# DCDC_DDS.net
KiCad netlist of a schematic drawn in Altium Designer
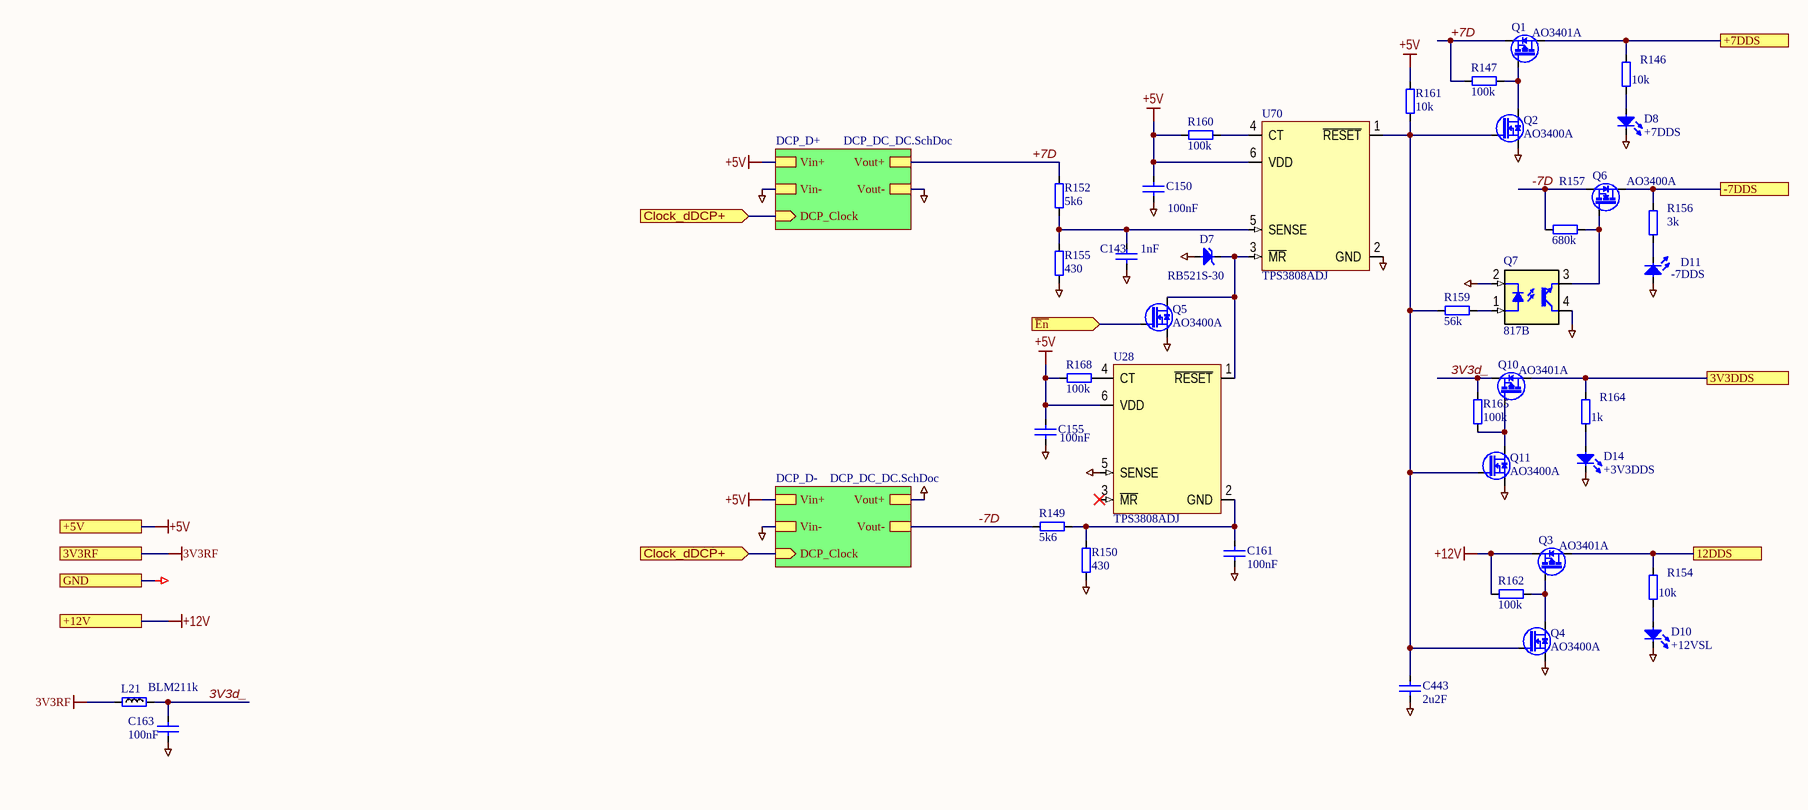
[diagram p0: DCDC_DDS.SchDoc]

(export (version "E")
  (design (tool "Eeschema 10.0.6"))
  (components
    (comp (ref "C143")
      (value "1nF")
      (footprint "SMD0805CAP")
      (description "Чип конденсатор 0805")
      (fields (field (name "VOLTAGE") "25V") (field (name "TOLERANCE") "20%"))
      (libsource (lib "DDSintLib") (part "C0805"))
    )
    (comp (ref "C150")
      (value "100nF")
      (footprint "SMD0805CAP")
      (description "Чип конденсатор 0805")
      (fields (field (name "VOLTAGE") "25V") (field (name "TOLERANCE") "20%"))
      (libsource (lib "DDSintLib") (part "C0805"))
    )
    (comp (ref "C155")
      (value "100nF")
      (footprint "SMD0805CAP")
      (description "Чип конденсатор 0805")
      (fields (field (name "VOLTAGE") "25V") (field (name "TOLERANCE") "20%"))
      (libsource (lib "DDSintLib") (part "C0805"))
    )
    (comp (ref "C161")
      (value "100nF")
      (footprint "SMD0805CAP")
      (description "Чип конденсатор 0805")
      (fields (field (name "VOLTAGE") "25V") (field (name "TOLERANCE") "20%"))
      (libsource (lib "DDSintLib") (part "C0805"))
    )
    (comp (ref "C163")
      (value "100nF")
      (footprint "SMD0805CAP")
      (description "Чип конденсатор 0805")
      (fields (field (name "VOLTAGE") "25V") (field (name "TOLERANCE") "20%"))
      (libsource (lib "DDSintLib") (part "C0805"))
    )
    (comp (ref "C443")
      (value "2u2F")
      (footprint "SMD0805CAP")
      (description "Чип конденсатор 0805")
      (fields (field (name "VOLTAGE") "25V") (field (name "TOLERANCE") "20%"))
      (libsource (lib "DDSintLib") (part "C0805"))
    )
    (comp (ref "D7")
      (value "RB521S-30")
      (footprint "SODFL1608X65N")
      (description "Чип Шоттки диод")
      (fields (field (name "VOLTAGE") "30V"))
      (libsource (lib "DDSintLib") (part "RB521S-30"))
    )
    (comp (ref "D8")
      (value "+7DDS")
      (footprint "LED0603")
      (description "Чип светодиод 0603")
      (libsource (lib "DDSintLib") (part "LED0603"))
    )
    (comp (ref "D10")
      (value "+12VSL")
      (footprint "LED0603")
      (description "Чип светодиод 0603")
      (libsource (lib "DDSintLib") (part "LED0603"))
    )
    (comp (ref "D11")
      (value "-7DDS")
      (footprint "LED0603")
      (description "Чип светодиод 0603")
      (libsource (lib "DDSintLib") (part "LED0603"))
    )
    (comp (ref "D14")
      (value "+3V3DDS")
      (footprint "LED0603")
      (description "Чип светодиод 0603")
      (libsource (lib "DDSintLib") (part "LED0603"))
    )
    (comp (ref "L21")
      (value "BLM211k")
      (footprint "RESC2012X50N")
      (description "SMD Ferrite bead 0805")
      (libsource (lib "DDSintLib") (part "BLM21"))
    )
    (comp (ref "Q1")
      (value "AO3401A")
      (footprint "SOT95P229X119-3N")
      (description "PMOS")
      (fields (field (name "VOLTAGE") "-30V"))
      (libsource (lib "DDSintLib") (part "AO3401A"))
    )
    (comp (ref "Q2")
      (value "AO3400A")
      (footprint "SOT95P229X119-3N")
      (description "NMOS")
      (fields (field (name "VOLTAGE") "30V"))
      (libsource (lib "DDSintLib") (part "AO3400A"))
    )
    (comp (ref "Q3")
      (value "AO3401A")
      (footprint "SOT95P229X119-3N")
      (description "PMOS")
      (fields (field (name "VOLTAGE") "-30V"))
      (libsource (lib "DDSintLib") (part "AO3401A"))
    )
    (comp (ref "Q4")
      (value "AO3400A")
      (footprint "SOT95P229X119-3N")
      (description "NMOS")
      (fields (field (name "VOLTAGE") "30V"))
      (libsource (lib "DDSintLib") (part "AO3400A"))
    )
    (comp (ref "Q5")
      (value "AO3400A")
      (footprint "SOT95P229X119-3N")
      (description "NMOS")
      (fields (field (name "VOLTAGE") "30V"))
      (libsource (lib "DDSintLib") (part "AO3400A"))
    )
    (comp (ref "Q6")
      (value "AO3400A")
      (footprint "SOT95P229X119-3N")
      (description "NMOS")
      (fields (field (name "VOLTAGE") "30V"))
      (libsource (lib "DDSintLib") (part "AO3400A"))
    )
    (comp (ref "Q7")
      (value "817B")
      (footprint "DIP4-300")
      (description "Optotransistor")
      (fields (field (name "VOLTAGE") "35V"))
      (libsource (lib "DDS1") (part "817B"))
    )
    (comp (ref "Q10")
      (value "AO3401A")
      (footprint "SOT95P229X119-3N")
      (description "PMOS")
      (fields (field (name "VOLTAGE") "-30V"))
      (libsource (lib "DDSintLib") (part "AO3401A"))
    )
    (comp (ref "Q11")
      (value "AO3400A")
      (footprint "SOT95P229X119-3N")
      (description "NMOS")
      (fields (field (name "VOLTAGE") "30V"))
      (libsource (lib "DDSintLib") (part "AO3400A"))
    )
    (comp (ref "R146")
      (value "10k")
      (footprint "SMD0805RES")
      (description "Чип резистор 0805")
      (fields (field (name "TOLERANCE") "1%"))
      (libsource (lib "DDSintLib") (part "R0805"))
    )
    (comp (ref "R147")
      (value "100k")
      (footprint "SMD0805RES")
      (description "Чип резистор 0805")
      (fields (field (name "TOLERANCE") "1%"))
      (libsource (lib "DDSintLib") (part "R0805"))
    )
    (comp (ref "R149")
      (value "5k6")
      (footprint "SMD0805RES")
      (description "Чип резистор 0805")
      (fields (field (name "TOLERANCE") "1%"))
      (libsource (lib "DDSintLib") (part "R0805"))
    )
    (comp (ref "R150")
      (value "430")
      (footprint "SMD0805RES")
      (description "Чип резистор 0805")
      (fields (field (name "TOLERANCE") "1%"))
      (libsource (lib "DDSintLib") (part "R0805"))
    )
    (comp (ref "R152")
      (value "5k6")
      (footprint "SMD0805RES")
      (description "Чип резистор 0805")
      (fields (field (name "TOLERANCE") "1%"))
      (libsource (lib "DDSintLib") (part "R0805"))
    )
    (comp (ref "R154")
      (value "10k")
      (footprint "SMD0805RES")
      (description "Чип резистор 0805")
      (fields (field (name "TOLERANCE") "1%"))
      (libsource (lib "DDSintLib") (part "R0805"))
    )
    (comp (ref "R155")
      (value "430")
      (footprint "SMD0805RES")
      (description "Чип резистор 0805")
      (fields (field (name "TOLERANCE") "1%"))
      (libsource (lib "DDSintLib") (part "R0805"))
    )
    (comp (ref "R156")
      (value "3k")
      (footprint "SMD0805RES")
      (description "Чип резистор 0805")
      (fields (field (name "TOLERANCE") "1%"))
      (libsource (lib "DDSintLib") (part "R0805"))
    )
    (comp (ref "R157")
      (value "680k")
      (footprint "SMD0805RES")
      (description "Чип резистор 0805")
      (fields (field (name "TOLERANCE") "1%"))
      (libsource (lib "DDSintLib") (part "R0805"))
    )
    (comp (ref "R159")
      (value "56k")
      (footprint "SMD0805RES")
      (description "Чип резистор 0805")
      (fields (field (name "TOLERANCE") "1%"))
      (libsource (lib "DDSintLib") (part "R0805"))
    )
    (comp (ref "R160")
      (value "100k")
      (footprint "SMD0805RES")
      (description "Чип резистор 0805")
      (fields (field (name "TOLERANCE") "1%"))
      (libsource (lib "DDSintLib") (part "R0805"))
    )
    (comp (ref "R161")
      (value "10k")
      (footprint "SMD0805RES")
      (description "Чип резистор 0805")
      (fields (field (name "TOLERANCE") "1%"))
      (libsource (lib "DDSintLib") (part "R0805"))
    )
    (comp (ref "R162")
      (value "100k")
      (footprint "SMD0805RES")
      (description "Чип резистор 0805")
      (fields (field (name "TOLERANCE") "1%"))
      (libsource (lib "DDSintLib") (part "R0805"))
    )
    (comp (ref "R164")
      (value "1k")
      (footprint "SMD0805RES")
      (description "Чип резистор 0805")
      (fields (field (name "TOLERANCE") "1%"))
      (libsource (lib "DDSintLib") (part "R0805"))
    )
    (comp (ref "R165")
      (value "100k")
      (footprint "SMD0805RES")
      (description "Чип резистор 0805")
      (fields (field (name "TOLERANCE") "1%"))
      (libsource (lib "DDSintLib") (part "R0805"))
    )
    (comp (ref "R168")
      (value "100k")
      (footprint "SMD0805RES")
      (description "Чип резистор 0805")
      (fields (field (name "TOLERANCE") "1%"))
      (libsource (lib "DDSintLib") (part "R0805"))
    )
    (comp (ref "U28")
      (value "TPS3808ADJ")
      (footprint "SOT95P270X145-6N")
      (description "Supervisory Circuit. Low-Quiescent-Current, Programmable-Delay")
      (libsource (lib "DDS1") (part "TPS3808"))
    )
    (comp (ref "U70")
      (value "TPS3808ADJ")
      (footprint "SOT95P270X145-6N")
      (description "Supervisory Circuit. Low-Quiescent-Current, Programmable-Delay")
      (libsource (lib "DDS1") (part "TPS3808"))
    )
  )
  (nets
    (net (code "1") (name "+5V") (class "Default")
      (node (ref "C150") (pin "2") (pinfunction "2_2") (pintype "passive"))
      (node (ref "C155") (pin "2") (pinfunction "2_2") (pintype "passive"))
      (node (ref "R160") (pin "1") (pinfunction "1_1") (pintype "passive"))
      (node (ref "R161") (pin "1") (pinfunction "1_1") (pintype "passive"))
      (node (ref "R168") (pin "1") (pinfunction "1_1") (pintype "passive"))
      (node (ref "U28") (pin "6") (pinfunction "VDD_6") (pintype "power_in"))
      (node (ref "U70") (pin "6") (pinfunction "VDD_6") (pintype "power_in"))
    )
    (net (code "2") (name "+12V") (class "Default")
      (node (ref "Q3") (pin "2") (pinfunction "S_2") (pintype "passive"))
      (node (ref "R162") (pin "2") (pinfunction "2_2") (pintype "passive"))
    )
    (net (code "3") (name "/+7D") (class "Default")
      (node (ref "Q1") (pin "2") (pinfunction "S_2") (pintype "passive"))
      (node (ref "R147") (pin "2") (pinfunction "2_2") (pintype "passive"))
      (node (ref "R152") (pin "1") (pinfunction "1_1") (pintype "passive"))
    )
    (net (code "4") (name "/+7DDS") (class "Default")
      (node (ref "Q1") (pin "3") (pinfunction "D_3") (pintype "passive"))
      (node (ref "R146") (pin "2") (pinfunction "2_2") (pintype "passive"))
    )
    (net (code "5") (name "/-7D") (class "Default")
      (node (ref "Q6") (pin "2") (pinfunction "S_2") (pintype "passive"))
      (node (ref "R149") (pin "1") (pinfunction "1_1") (pintype "passive"))
      (node (ref "R157") (pin "2") (pinfunction "2_2") (pintype "passive"))
    )
    (net (code "6") (name "/-7DDS") (class "Default")
      (node (ref "Q6") (pin "3") (pinfunction "D_3") (pintype "passive"))
      (node (ref "R156") (pin "2") (pinfunction "2_2") (pintype "passive"))
    )
    (net (code "7") (name "/3V3DDS") (class "Default")
      (node (ref "Q10") (pin "3") (pinfunction "D_3") (pintype "passive"))
      (node (ref "R164") (pin "2") (pinfunction "2_2") (pintype "passive"))
    )
    (net (code "8") (name "/3V3d_") (class "Default")
      (node (ref "C163") (pin "2") (pinfunction "2_2") (pintype "passive"))
      (node (ref "L21") (pin "1") (pinfunction "1_1") (pintype "passive"))
      (node (ref "Q10") (pin "2") (pinfunction "S_2") (pintype "passive"))
      (node (ref "R165") (pin "1") (pinfunction "1_1") (pintype "passive"))
    )
    (net (code "9") (name "/12DDS") (class "Default")
      (node (ref "Q3") (pin "3") (pinfunction "D_3") (pintype "passive"))
      (node (ref "R154") (pin "2") (pinfunction "2_2") (pintype "passive"))
    )
    (net (code "11") (name "/En") (class "Default")
      (node (ref "Q5") (pin "1") (pinfunction "G_1") (pintype "passive"))
    )
    (net (code "12") (name "3V3RF") (class "Default")
      (node (ref "L21") (pin "2") (pinfunction "2_2") (pintype "passive"))
    )
    (net (code "13") (name "GND") (class "Default")
      (node (ref "C143") (pin "1") (pinfunction "1_1") (pintype "passive"))
      (node (ref "C150") (pin "1") (pinfunction "1_1") (pintype "passive"))
      (node (ref "C155") (pin "1") (pinfunction "1_1") (pintype "passive"))
      (node (ref "C161") (pin "2") (pinfunction "2_2") (pintype "passive"))
      (node (ref "C163") (pin "1") (pinfunction "1_1") (pintype "passive"))
      (node (ref "C443") (pin "2") (pinfunction "2_2") (pintype "passive"))
      (node (ref "D10") (pin "1") (pinfunction "C_1") (pintype "passive"))
      (node (ref "D11") (pin "2") (pinfunction "A_2") (pintype "passive"))
      (node (ref "D14") (pin "1") (pinfunction "C_1") (pintype "passive"))
      (node (ref "D7") (pin "2") (pinfunction "A_2") (pintype "passive"))
      (node (ref "D8") (pin "1") (pinfunction "C_1") (pintype "passive"))
      (node (ref "Q11") (pin "2") (pinfunction "S_2") (pintype "passive"))
      (node (ref "Q2") (pin "2") (pinfunction "S_2") (pintype "passive"))
      (node (ref "Q4") (pin "2") (pinfunction "S_2") (pintype "passive"))
      (node (ref "Q5") (pin "2") (pinfunction "S_2") (pintype "passive"))
      (node (ref "Q7") (pin "2") (pinfunction "C_2") (pintype "input"))
      (node (ref "Q7") (pin "4") (pinfunction "C_4") (pintype "open_collector"))
      (node (ref "R150") (pin "1") (pinfunction "1_1") (pintype "passive"))
      (node (ref "R155") (pin "1") (pinfunction "1_1") (pintype "passive"))
      (node (ref "U28") (pin "5") (pinfunction "SENSE_5") (pintype "input"))
      (node (ref "U70") (pin "2") (pinfunction "GND_2") (pintype "power_in"))
    )
    (net (code "14") (name "Net-(D7-C)") (class "Default")
      (node (ref "D7") (pin "1") (pinfunction "C_1") (pintype "passive"))
      (node (ref "Q5") (pin "3") (pinfunction "D_3") (pintype "passive"))
      (node (ref "U28") (pin "1") (pinfunction "~{RESET}_1") (pintype "open_collector"))
      (node (ref "U70") (pin "3") (pinfunction "~{MR}_3") (pintype "input"))
    )
    (net (code "15") (name "Net-(D8-A)") (class "Default")
      (node (ref "D8") (pin "2") (pinfunction "A_2") (pintype "passive"))
      (node (ref "R146") (pin "1") (pinfunction "1_1") (pintype "passive"))
    )
    (net (code "16") (name "Net-(D10-A)") (class "Default")
      (node (ref "D10") (pin "2") (pinfunction "A_2") (pintype "passive"))
      (node (ref "R154") (pin "1") (pinfunction "1_1") (pintype "passive"))
    )
    (net (code "17") (name "Net-(D11-C)") (class "Default")
      (node (ref "D11") (pin "1") (pinfunction "C_1") (pintype "passive"))
      (node (ref "R156") (pin "1") (pinfunction "1_1") (pintype "passive"))
    )
    (net (code "18") (name "Net-(D14-A)") (class "Default")
      (node (ref "D14") (pin "2") (pinfunction "A_2") (pintype "passive"))
      (node (ref "R164") (pin "1") (pinfunction "1_1") (pintype "passive"))
    )
    (net (code "19") (name "Net-(Q1-G)") (class "Default")
      (node (ref "Q1") (pin "1") (pinfunction "G_1") (pintype "passive"))
      (node (ref "Q2") (pin "3") (pinfunction "D_3") (pintype "passive"))
      (node (ref "R147") (pin "1") (pinfunction "1_1") (pintype "passive"))
    )
    (net (code "20") (name "Net-(Q3-G)") (class "Default")
      (node (ref "Q3") (pin "1") (pinfunction "G_1") (pintype "passive"))
      (node (ref "Q4") (pin "3") (pinfunction "D_3") (pintype "passive"))
      (node (ref "R162") (pin "1") (pinfunction "1_1") (pintype "passive"))
    )
    (net (code "21") (name "Net-(Q6-G)") (class "Default")
      (node (ref "Q6") (pin "1") (pinfunction "G_1") (pintype "passive"))
      (node (ref "Q7") (pin "3") (pinfunction "E_3") (pintype "open_emitter"))
      (node (ref "R157") (pin "1") (pinfunction "1_1") (pintype "passive"))
    )
    (net (code "22") (name "Net-(Q7-A)") (class "Default")
      (node (ref "Q7") (pin "1") (pinfunction "A_1") (pintype "input"))
      (node (ref "R159") (pin "2") (pinfunction "2_2") (pintype "passive"))
    )
    (net (code "23") (name "Net-(Q10-G)") (class "Default")
      (node (ref "Q10") (pin "1") (pinfunction "G_1") (pintype "passive"))
      (node (ref "Q11") (pin "3") (pinfunction "D_3") (pintype "passive"))
      (node (ref "R165") (pin "2") (pinfunction "2_2") (pintype "passive"))
    )
    (net (code "24") (name "Net-(Q11-G)") (class "Default")
      (node (ref "C443") (pin "1") (pinfunction "1_1") (pintype "passive"))
      (node (ref "Q11") (pin "1") (pinfunction "G_1") (pintype "passive"))
      (node (ref "Q2") (pin "1") (pinfunction "G_1") (pintype "passive"))
      (node (ref "Q4") (pin "1") (pinfunction "G_1") (pintype "passive"))
      (node (ref "R159") (pin "1") (pinfunction "1_1") (pintype "passive"))
      (node (ref "R161") (pin "2") (pinfunction "2_2") (pintype "passive"))
      (node (ref "U70") (pin "1") (pinfunction "~{RESET}_1") (pintype "open_collector"))
    )
    (net (code "25") (name "Net-(U28-CT)") (class "Default")
      (node (ref "R168") (pin "2") (pinfunction "2_2") (pintype "passive"))
      (node (ref "U28") (pin "4") (pinfunction "CT_4") (pintype "passive"))
    )
    (net (code "26") (name "Net-(U28-GND)") (class "Default")
      (node (ref "C161") (pin "1") (pinfunction "1_1") (pintype "passive"))
      (node (ref "R149") (pin "2") (pinfunction "2_2") (pintype "passive"))
      (node (ref "R150") (pin "2") (pinfunction "2_2") (pintype "passive"))
      (node (ref "U28") (pin "2") (pinfunction "GND_2") (pintype "power_in"))
    )
    (net (code "27") (name "Net-(U70-CT)") (class "Default")
      (node (ref "R160") (pin "2") (pinfunction "2_2") (pintype "passive"))
      (node (ref "U70") (pin "4") (pinfunction "CT_4") (pintype "passive"))
    )
    (net (code "28") (name "Net-(U70-SENSE)") (class "Default")
      (node (ref "C143") (pin "2") (pinfunction "2_2") (pintype "passive"))
      (node (ref "R152") (pin "2") (pinfunction "2_2") (pintype "passive"))
      (node (ref "R155") (pin "2") (pinfunction "2_2") (pintype "passive"))
      (node (ref "U70") (pin "5") (pinfunction "SENSE_5") (pintype "input"))
    )
    (net (code "29") (name "unconnected-(U28-~{MR}-Pad3)") (class "Default")
      (node (ref "U28") (pin "3") (pinfunction "~{MR}_3") (pintype "input+no_connect"))
    )
  )
)
